# main.net
KiCad netlist of a schematic drawn in Altium Designer
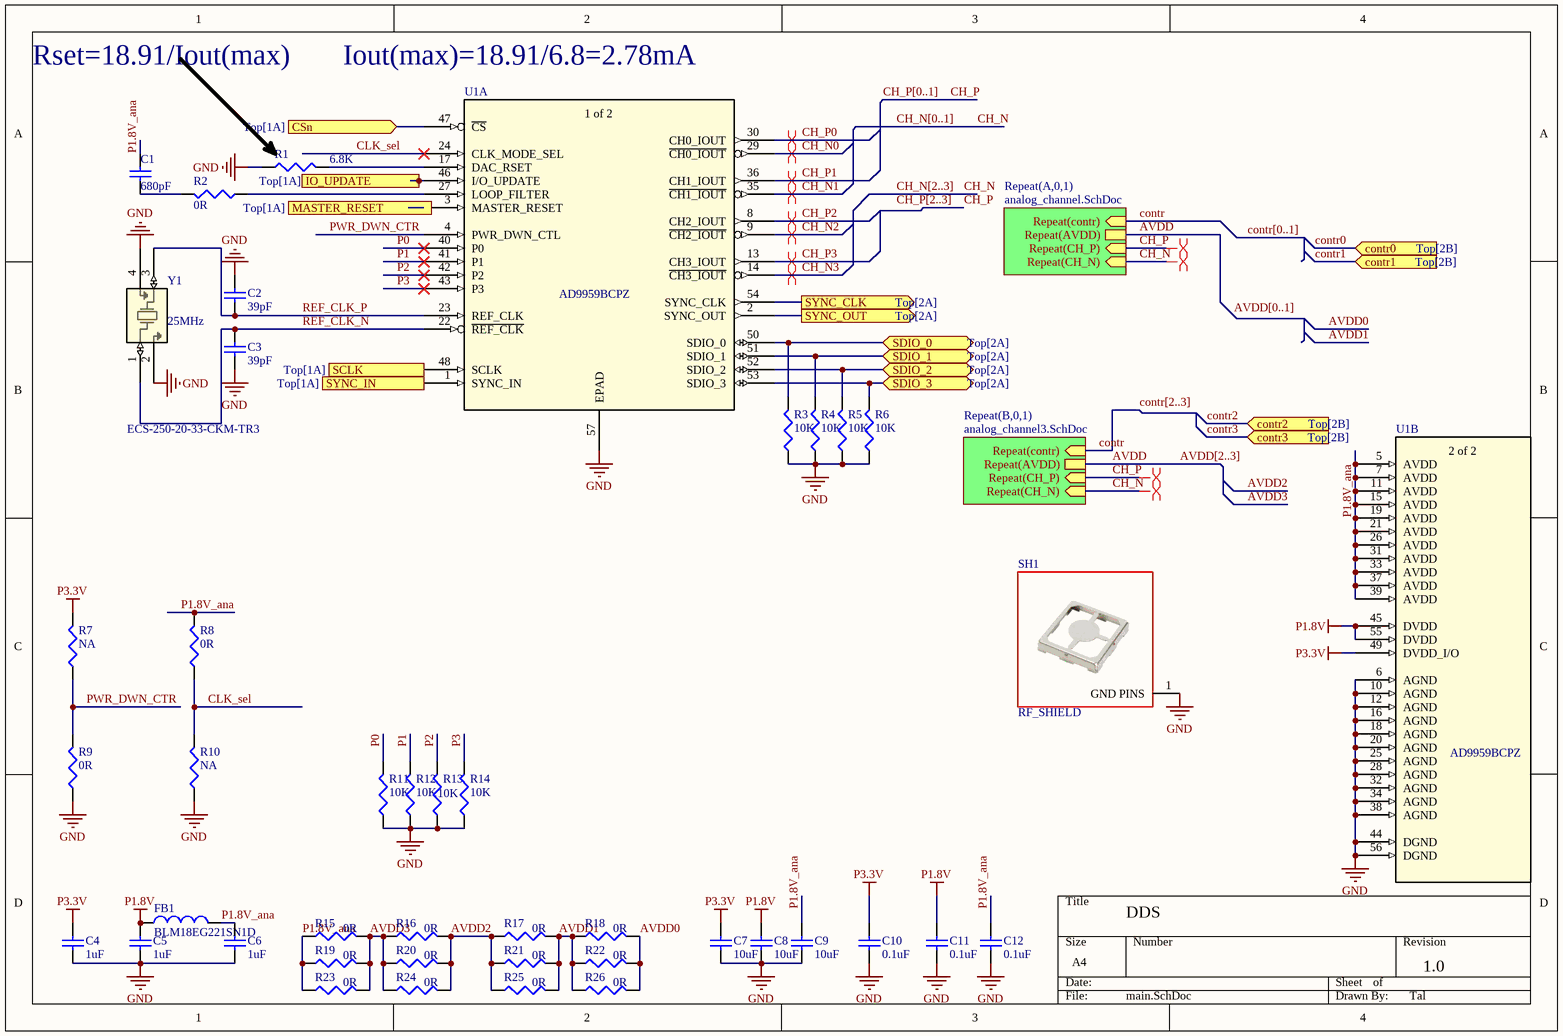
[diagram p0: main.SchDoc]

(export (version "E")
  (design (tool "Eeschema 10.0.6"))
  (components
    (comp (ref "C1")
      (value "680pF 50V")
      (footprint "C0402")
      (description "CAP CER 680PF 50V NP0 0402")
      (fields
        (field (name "MANUFACTURER PART NUMBER") "C1005C0G1H6R8D")
        (field (name "MANUFACTURER") "TDK Corporation")
        (field (name "CAPACITANCE") "680pF")
      )
      (libsource (lib "L_SCH_C") (part "CAP CER 6.8pF 50V NP0 0402"))
    )
    (comp (ref "C2")
      (value "39pF 50V")
      (footprint "C0402")
      (description "CAP CER 39PF 50V NP0 0402")
      (fields
        (field (name "MANUFACTURER PART NUMBER") "C1005C0G1H6R8D")
        (field (name "MANUFACTURER") "TDK Corporation")
        (field (name "CAPACITANCE") "39pF")
      )
      (libsource (lib "L_SCH_C") (part "CAP CER 6.8pF 50V NP0 0402"))
    )
    (comp (ref "C3")
      (value "39pF 50V")
      (footprint "C0402")
      (description "CAP CER 39PF 50V NP0 0402")
      (fields
        (field (name "MANUFACTURER PART NUMBER") "C1005C0G1H6R8D")
        (field (name "MANUFACTURER") "TDK Corporation")
        (field (name "CAPACITANCE") "39pF")
      )
      (libsource (lib "L_SCH_C") (part "CAP CER 6.8pF 50V NP0 0402"))
    )
    (comp (ref "C4")
      (value "1uF 25V")
      (footprint "C0402")
      (description "CAP CER 1uF 25V X5R 0402")
      (fields
        (field (name "MANUFACTURER PART NUMBER") "C1005C0G1H6R8D")
        (field (name "MANUFACTURER") "TDK Corporation")
        (field (name "CAPACITANCE") "1uF")
      )
      (libsource (lib "L_SCH_C") (part "CAP CER 6.8pF 50V NP0 0402"))
    )
    (comp (ref "C5")
      (value "1uF 25V")
      (footprint "C0402")
      (description "CAP CER 1uF 25V X5R 0402")
      (fields
        (field (name "MANUFACTURER PART NUMBER") "C1005C0G1H6R8D")
        (field (name "MANUFACTURER") "TDK Corporation")
        (field (name "CAPACITANCE") "1uF")
      )
      (libsource (lib "L_SCH_C") (part "CAP CER 6.8pF 50V NP0 0402"))
    )
    (comp (ref "C6")
      (value "1uF 25V")
      (footprint "C0402")
      (description "CAP CER 1uF 25V X5R 0402")
      (fields
        (field (name "MANUFACTURER PART NUMBER") "C1005C0G1H6R8D")
        (field (name "MANUFACTURER") "TDK Corporation")
        (field (name "CAPACITANCE") "1uF")
      )
      (libsource (lib "L_SCH_C") (part "CAP CER 6.8pF 50V NP0 0402"))
    )
    (comp (ref "C7")
      (value "10uF 10V")
      (footprint "C0402")
      (description "CAP CER 10uF 10V X5R 0402")
      (fields
        (field (name "MANUFACTURER PART NUMBER") "C1005C0G1H6R8D")
        (field (name "MANUFACTURER") "TDK Corporation")
        (field (name "CAPACITANCE") "10uF")
      )
      (libsource (lib "L_SCH_C") (part "CAP CER 6.8pF 50V NP0 0402"))
    )
    (comp (ref "C8")
      (value "10uF 10V")
      (footprint "C0402")
      (description "CAP CER 10uF 10V X5R 0402")
      (fields
        (field (name "MANUFACTURER PART NUMBER") "C1005C0G1H6R8D")
        (field (name "MANUFACTURER") "TDK Corporation")
        (field (name "CAPACITANCE") "10uF")
      )
      (libsource (lib "L_SCH_C") (part "CAP CER 6.8pF 50V NP0 0402"))
    )
    (comp (ref "C9")
      (value "10uF 10V")
      (footprint "C0402")
      (description "CAP CER 10uF 10V X5R 0402")
      (fields
        (field (name "MANUFACTURER PART NUMBER") "C1005C0G1H6R8D")
        (field (name "MANUFACTURER") "TDK Corporation")
        (field (name "CAPACITANCE") "10uF")
      )
      (libsource (lib "L_SCH_C") (part "CAP CER 6.8pF 50V NP0 0402"))
    )
    (comp (ref "C10")
      (value "0.1uF 50V")
      (footprint "C0402")
      (description "CAP CER 0.1uF 50V NP0 0402")
      (fields
        (field (name "MANUFACTURER PART NUMBER") "C1005C0G1H6R8D")
        (field (name "MANUFACTURER") "TDK Corporation")
        (field (name "CAPACITANCE") "0.1uF")
      )
      (libsource (lib "L_SCH_C") (part "CAP CER 6.8pF 50V NP0 0402"))
    )
    (comp (ref "C11")
      (value "0.1uF 50V")
      (footprint "C0402")
      (description "CAP CER 0.1uF 50V NP0 0402")
      (fields
        (field (name "MANUFACTURER PART NUMBER") "C1005C0G1H6R8D")
        (field (name "MANUFACTURER") "TDK Corporation")
        (field (name "CAPACITANCE") "0.1uF")
      )
      (libsource (lib "L_SCH_C") (part "CAP CER 6.8pF 50V NP0 0402"))
    )
    (comp (ref "C12")
      (value "0.1uF 50V")
      (footprint "C0402")
      (description "CAP CER 0.1uF 50V NP0 0402")
      (fields
        (field (name "MANUFACTURER PART NUMBER") "C1005C0G1H6R8D")
        (field (name "MANUFACTURER") "TDK Corporation")
        (field (name "CAPACITANCE") "0.1uF")
      )
      (libsource (lib "L_SCH_C") (part "CAP CER 6.8pF 50V NP0 0402"))
    )
    (comp (ref "FB1")
      (value "BLM18EG221SN1D")
      (footprint "fb0603")
      (description "FERRITE BEAD 220_OHM@100MHz 0603 2A 50mohm_DC")
      (fields
        (field (name "MANUFACTURER") "Taiyo Yuden")
        (field (name "MANUFACTURER PART NUMBER") "BLM18EG221SN1D")
      )
      (libsource (lib "L_SCH") (part "BK1608HS600-T"))
    )
    (comp (ref "R1")
      (value "6.8K")
      (footprint "R0402")
      (description "RES 6.8K OHM 1/16W 1% 0402")
      (fields
        (field (name "MANUFACTURER PART NUMBER") "RMCF0402FT3K09")
        (field (name "MANUFACTURER") "Stackpole Electronics Inc")
      )
      (libsource (lib "L_SCH_R") (part "RES 3.09K OHM 1/16W 1% 0402"))
    )
    (comp (ref "R2")
      (value "0R")
      (footprint "R0402")
      (description "RES 0 OHM 1/10W 1% 0402 SMD")
      (fields
        (field (name "MANUFACTURER PART NUMBER") "ERJ-2RKF1000X")
        (field (name "MANUFACTURER") "Panasonic Electronic Components")
      )
      (libsource (lib "L_SCH_R") (part "RES 100 OHM 1/10W 1% 0402 SMD"))
    )
    (comp (ref "R3")
      (value "10K")
      (footprint "R0402")
      (description "RES 10K OHM 1/16W 1% 0402")
      (fields
        (field (name "MANUFACTURER PART NUMBER") "RMCF0402FT3K09")
        (field (name "MANUFACTURER") "Stackpole Electronics Inc")
      )
      (libsource (lib "L_SCH_R") (part "RES 3.09K OHM 1/16W 1% 0402"))
    )
    (comp (ref "R4")
      (value "10K")
      (footprint "R0402")
      (description "RES 10K OHM 1/16W 1% 0402")
      (fields
        (field (name "MANUFACTURER PART NUMBER") "RMCF0402FT3K09")
        (field (name "MANUFACTURER") "Stackpole Electronics Inc")
      )
      (libsource (lib "L_SCH_R") (part "RES 3.09K OHM 1/16W 1% 0402"))
    )
    (comp (ref "R5")
      (value "10K")
      (footprint "R0402")
      (description "RES 10K OHM 1/16W 1% 0402")
      (fields
        (field (name "MANUFACTURER PART NUMBER") "RMCF0402FT3K09")
        (field (name "MANUFACTURER") "Stackpole Electronics Inc")
      )
      (libsource (lib "L_SCH_R") (part "RES 3.09K OHM 1/16W 1% 0402"))
    )
    (comp (ref "R6")
      (value "10K")
      (footprint "R0402")
      (description "RES 10K OHM 1/16W 1% 0402")
      (fields
        (field (name "MANUFACTURER PART NUMBER") "RMCF0402FT3K09")
        (field (name "MANUFACTURER") "Stackpole Electronics Inc")
      )
      (libsource (lib "L_SCH_R") (part "RES 3.09K OHM 1/16W 1% 0402"))
    )
    (comp (ref "R7")
      (value "NA")
      (footprint "R0402")
      (description "RES 0 OHM 1/10W 1% 0402 SMD")
      (fields
        (field (name "MANUFACTURER PART NUMBER") "ERJ-2RKF1000X")
        (field (name "MANUFACTURER") "Panasonic Electronic Components")
      )
      (libsource (lib "L_SCH_R") (part "RES 100 OHM 1/10W 1% 0402 SMD"))
    )
    (comp (ref "R8")
      (value "0R")
      (footprint "R0402")
      (description "RES 0 OHM 1/10W 1% 0402 SMD")
      (fields
        (field (name "MANUFACTURER PART NUMBER") "ERJ-2RKF1000X")
        (field (name "MANUFACTURER") "Panasonic Electronic Components")
      )
      (libsource (lib "L_SCH_R") (part "RES 100 OHM 1/10W 1% 0402 SMD"))
    )
    (comp (ref "R9")
      (value "0R")
      (footprint "R0402")
      (description "RES 0 OHM 1/10W 1% 0402 SMD")
      (fields
        (field (name "MANUFACTURER PART NUMBER") "ERJ-2RKF1000X")
        (field (name "MANUFACTURER") "Panasonic Electronic Components")
      )
      (libsource (lib "L_SCH_R") (part "RES 100 OHM 1/10W 1% 0402 SMD"))
    )
    (comp (ref "R10")
      (value "NA")
      (footprint "R0402")
      (description "RES 0 OHM 1/10W 1% 0402 SMD")
      (fields
        (field (name "MANUFACTURER PART NUMBER") "ERJ-2RKF1000X")
        (field (name "MANUFACTURER") "Panasonic Electronic Components")
      )
      (libsource (lib "L_SCH_R") (part "RES 100 OHM 1/10W 1% 0402 SMD"))
    )
    (comp (ref "R11")
      (value "10K")
      (footprint "R0402")
      (description "RES 10K OHM 1/16W 1% 0402")
      (fields
        (field (name "MANUFACTURER PART NUMBER") "RMCF0402FT3K09")
        (field (name "MANUFACTURER") "Stackpole Electronics Inc")
      )
      (libsource (lib "L_SCH_R") (part "RES 3.09K OHM 1/16W 1% 0402"))
    )
    (comp (ref "R12")
      (value "10K")
      (footprint "R0402")
      (description "RES 10K OHM 1/16W 1% 0402")
      (fields
        (field (name "MANUFACTURER PART NUMBER") "RMCF0402FT3K09")
        (field (name "MANUFACTURER") "Stackpole Electronics Inc")
      )
      (libsource (lib "L_SCH_R") (part "RES 3.09K OHM 1/16W 1% 0402"))
    )
    (comp (ref "R13")
      (value "10K")
      (footprint "R0402")
      (description "RES 10K OHM 1/16W 1% 0402")
      (fields
        (field (name "MANUFACTURER PART NUMBER") "RMCF0402FT3K09")
        (field (name "MANUFACTURER") "Stackpole Electronics Inc")
      )
      (libsource (lib "L_SCH_R") (part "RES 3.09K OHM 1/16W 1% 0402"))
    )
    (comp (ref "R14")
      (value "10K")
      (footprint "R0402")
      (description "RES 10K OHM 1/16W 1% 0402")
      (fields
        (field (name "MANUFACTURER PART NUMBER") "RMCF0402FT3K09")
        (field (name "MANUFACTURER") "Stackpole Electronics Inc")
      )
      (libsource (lib "L_SCH_R") (part "RES 3.09K OHM 1/16W 1% 0402"))
    )
    (comp (ref "R15")
      (value "0R")
      (footprint "R0805")
      (description "RES 0 OHM 1/8W 1% 0805 SMD")
      (fields
        (field (name "MANUFACTURER PART NUMBER") "RMCF0805FT200R")
        (field (name "MANUFACTURER") "Stackpole Electronics Inc")
      )
      (libsource (lib "L_SCH_R") (part "RES 200 OHM 1/8W 1% 0805 SMD"))
    )
    (comp (ref "R16")
      (value "0R")
      (footprint "R0805")
      (description "RES 0 OHM 1/8W 1% 0805 SMD")
      (fields
        (field (name "MANUFACTURER PART NUMBER") "RMCF0805FT200R")
        (field (name "MANUFACTURER") "Stackpole Electronics Inc")
      )
      (libsource (lib "L_SCH_R") (part "RES 200 OHM 1/8W 1% 0805 SMD"))
    )
    (comp (ref "R17")
      (value "0R")
      (footprint "R0805")
      (description "RES 0 OHM 1/8W 1% 0805 SMD")
      (fields
        (field (name "MANUFACTURER PART NUMBER") "RMCF0805FT200R")
        (field (name "MANUFACTURER") "Stackpole Electronics Inc")
      )
      (libsource (lib "L_SCH_R") (part "RES 200 OHM 1/8W 1% 0805 SMD"))
    )
    (comp (ref "R18")
      (value "0R")
      (footprint "R0805")
      (description "RES 0 OHM 1/8W 1% 0805 SMD")
      (fields
        (field (name "MANUFACTURER PART NUMBER") "RMCF0805FT200R")
        (field (name "MANUFACTURER") "Stackpole Electronics Inc")
      )
      (libsource (lib "L_SCH_R") (part "RES 200 OHM 1/8W 1% 0805 SMD"))
    )
    (comp (ref "R19")
      (value "0R")
      (footprint "R0805")
      (description "RES 0 OHM 1/8W 1% 0805 SMD")
      (fields
        (field (name "MANUFACTURER PART NUMBER") "RMCF0805FT200R")
        (field (name "MANUFACTURER") "Stackpole Electronics Inc")
      )
      (libsource (lib "L_SCH_R") (part "RES 200 OHM 1/8W 1% 0805 SMD"))
    )
    (comp (ref "R20")
      (value "0R")
      (footprint "R0805")
      (description "RES 0 OHM 1/8W 1% 0805 SMD")
      (fields
        (field (name "MANUFACTURER PART NUMBER") "RMCF0805FT200R")
        (field (name "MANUFACTURER") "Stackpole Electronics Inc")
      )
      (libsource (lib "L_SCH_R") (part "RES 200 OHM 1/8W 1% 0805 SMD"))
    )
    (comp (ref "R21")
      (value "0R")
      (footprint "R0805")
      (description "RES 0 OHM 1/8W 1% 0805 SMD")
      (fields
        (field (name "MANUFACTURER PART NUMBER") "RMCF0805FT200R")
        (field (name "MANUFACTURER") "Stackpole Electronics Inc")
      )
      (libsource (lib "L_SCH_R") (part "RES 200 OHM 1/8W 1% 0805 SMD"))
    )
    (comp (ref "R22")
      (value "0R")
      (footprint "R0805")
      (description "RES 0 OHM 1/8W 1% 0805 SMD")
      (fields
        (field (name "MANUFACTURER PART NUMBER") "RMCF0805FT200R")
        (field (name "MANUFACTURER") "Stackpole Electronics Inc")
      )
      (libsource (lib "L_SCH_R") (part "RES 200 OHM 1/8W 1% 0805 SMD"))
    )
    (comp (ref "R23")
      (value "0R")
      (footprint "R0805")
      (description "RES 0 OHM 1/8W 1% 0805 SMD")
      (fields
        (field (name "MANUFACTURER PART NUMBER") "RMCF0805FT200R")
        (field (name "MANUFACTURER") "Stackpole Electronics Inc")
      )
      (libsource (lib "L_SCH_R") (part "RES 200 OHM 1/8W 1% 0805 SMD"))
    )
    (comp (ref "R24")
      (value "0R")
      (footprint "R0805")
      (description "RES 0 OHM 1/8W 1% 0805 SMD")
      (fields
        (field (name "MANUFACTURER PART NUMBER") "RMCF0805FT200R")
        (field (name "MANUFACTURER") "Stackpole Electronics Inc")
      )
      (libsource (lib "L_SCH_R") (part "RES 200 OHM 1/8W 1% 0805 SMD"))
    )
    (comp (ref "R25")
      (value "0R")
      (footprint "R0805")
      (description "RES 0 OHM 1/8W 1% 0805 SMD")
      (fields
        (field (name "MANUFACTURER PART NUMBER") "RMCF0805FT200R")
        (field (name "MANUFACTURER") "Stackpole Electronics Inc")
      )
      (libsource (lib "L_SCH_R") (part "RES 200 OHM 1/8W 1% 0805 SMD"))
    )
    (comp (ref "R26")
      (value "0R")
      (footprint "R0805")
      (description "RES 0 OHM 1/8W 1% 0805 SMD")
      (fields
        (field (name "MANUFACTURER PART NUMBER") "RMCF0805FT200R")
        (field (name "MANUFACTURER") "Stackpole Electronics Inc")
      )
      (libsource (lib "L_SCH_R") (part "RES 200 OHM 1/8W 1% 0805 SMD"))
    )
    (comp (ref "SH1")
      (value "RF_SHIELD")
      (footprint "SMS201F")
      (description "RF SHIELD 0.5\" X 0.538\" SMD")
      (fields
        (field (name "MANUFACTURER_PART_NUMBER") "SMS-201F")
        (field (name "MANUFACTURER") "Leader Tech Inc.")
      )
      (libsource (lib "DDS_PCB_1") (part "RF_SHIELD"))
    )
    (comp (ref "U1")
      (value "AD9959BCPZ")
      (footprint "CP_56_1_ADI")
      (description "No Description Available")
      (fields (field (name "COPYRIGHT") "Copyright (C) 2023 Ultra Librarian. All rights reserved."))
      (libsource (lib "") (part "AD9959BCPZ_1"))
    )
    (comp (ref "Y1")
      (value "ECS-250-20-33-CKM-TR3")
      (footprint "SMD4_ECX-32_3p2x2p5_ECS")
      (description "No Description Available")
      (fields (field (name "COPYRIGHT") "Copyright (C) 2023 Ultra Librarian. All rights reserved."))
      (libsource (lib "ECS-250-20-33-CKM-TR3") (part "ECS-250-20-33-CKM-TR3"))
    )
  )
  (nets
    (net (code "2") (name "/AVDD0") (class "Default")
      (node (ref "R18") (pin "2") (pinfunction "2_2") (pintype "passive"))
      (node (ref "R22") (pin "2") (pinfunction "2_2") (pintype "passive"))
      (node (ref "R26") (pin "2") (pinfunction "2_2") (pintype "passive"))
    )
    (net (code "3") (name "/AVDD1") (class "Default")
      (node (ref "R17") (pin "2") (pinfunction "2_2") (pintype "passive"))
      (node (ref "R18") (pin "1") (pinfunction "1_1") (pintype "passive"))
      (node (ref "R21") (pin "2") (pinfunction "2_2") (pintype "passive"))
      (node (ref "R22") (pin "1") (pinfunction "1_1") (pintype "passive"))
      (node (ref "R25") (pin "2") (pinfunction "2_2") (pintype "passive"))
      (node (ref "R26") (pin "1") (pinfunction "1_1") (pintype "passive"))
    )
    (net (code "4") (name "/AVDD2") (class "Default")
      (node (ref "R16") (pin "2") (pinfunction "2_2") (pintype "passive"))
      (node (ref "R17") (pin "1") (pinfunction "1_1") (pintype "passive"))
      (node (ref "R20") (pin "2") (pinfunction "2_2") (pintype "passive"))
      (node (ref "R21") (pin "1") (pinfunction "1_1") (pintype "passive"))
      (node (ref "R24") (pin "2") (pinfunction "2_2") (pintype "passive"))
      (node (ref "R25") (pin "1") (pinfunction "1_1") (pintype "passive"))
    )
    (net (code "5") (name "/AVDD3") (class "Default")
      (node (ref "R15") (pin "2") (pinfunction "2_2") (pintype "passive"))
      (node (ref "R16") (pin "1") (pinfunction "1_1") (pintype "passive"))
      (node (ref "R19") (pin "2") (pinfunction "2_2") (pintype "passive"))
      (node (ref "R20") (pin "1") (pinfunction "1_1") (pintype "passive"))
      (node (ref "R23") (pin "2") (pinfunction "2_2") (pintype "passive"))
      (node (ref "R24") (pin "1") (pinfunction "1_1") (pintype "passive"))
    )
    (net (code "8") (name "/CH_N0") (class "Default")
      (node (ref "U1") (pin "29") (pinfunction "~{CH0_IOUT}_29") (pintype "output"))
    )
    (net (code "9") (name "/CH_N1") (class "Default")
      (node (ref "U1") (pin "35") (pinfunction "~{CH1_IOUT}_35") (pintype "output"))
    )
    (net (code "10") (name "/CH_N2") (class "Default")
      (node (ref "U1") (pin "9") (pinfunction "~{CH2_IOUT}_9") (pintype "output"))
    )
    (net (code "11") (name "/CH_N3") (class "Default")
      (node (ref "U1") (pin "14") (pinfunction "~{CH3_IOUT}_14") (pintype "output"))
    )
    (net (code "15") (name "/CH_P0") (class "Default")
      (node (ref "U1") (pin "30") (pinfunction "CH0_IOUT_30") (pintype "output"))
    )
    (net (code "16") (name "/CH_P1") (class "Default")
      (node (ref "U1") (pin "36") (pinfunction "CH1_IOUT_36") (pintype "output"))
    )
    (net (code "17") (name "/CH_P2") (class "Default")
      (node (ref "U1") (pin "8") (pinfunction "CH2_IOUT_8") (pintype "output"))
    )
    (net (code "18") (name "/CH_P3") (class "Default")
      (node (ref "U1") (pin "13") (pinfunction "CH3_IOUT_13") (pintype "output"))
    )
    (net (code "21") (name "/CLK_sel") (class "Default")
      (node (ref "R10") (pin "2") (pinfunction "2_2") (pintype "passive"))
      (node (ref "R8") (pin "1") (pinfunction "1_1") (pintype "passive"))
      (node (ref "U1") (pin "24") (pinfunction "CLK_MODE_SEL_24") (pintype "input"))
    )
    (net (code "22") (name "/CSn") (class "Default")
      (node (ref "U1") (pin "47") (pinfunction "~{CS}_47") (pintype "input"))
    )
    (net (code "23") (name "/IO_UPDATE") (class "Default")
      (node (ref "U1") (pin "46") (pinfunction "I/O_UPDATE_46") (pintype "input"))
    )
    (net (code "25") (name "/P0") (class "Default")
      (node (ref "R11") (pin "2") (pinfunction "2_2") (pintype "passive"))
      (node (ref "U1") (pin "40") (pinfunction "P0_40") (pintype "input"))
    )
    (net (code "26") (name "/P1") (class "Default")
      (node (ref "R12") (pin "2") (pinfunction "2_2") (pintype "passive"))
      (node (ref "U1") (pin "41") (pinfunction "P1_41") (pintype "input"))
    )
    (net (code "27") (name "/P1.8V_ana") (class "Default")
      (node (ref "C1") (pin "1") (pinfunction "1_1") (pintype "passive"))
      (node (ref "C12") (pin "2") (pinfunction "2_2") (pintype "passive"))
      (node (ref "C6") (pin "2") (pinfunction "2_2") (pintype "passive"))
      (node (ref "C9") (pin "2") (pinfunction "2_2") (pintype "passive"))
      (node (ref "FB1") (pin "2") (pinfunction "2_2") (pintype "passive"))
      (node (ref "R15") (pin "1") (pinfunction "1_1") (pintype "passive"))
      (node (ref "R19") (pin "1") (pinfunction "1_1") (pintype "passive"))
      (node (ref "R23") (pin "1") (pinfunction "1_1") (pintype "passive"))
      (node (ref "R8") (pin "2") (pinfunction "2_2") (pintype "passive"))
      (node (ref "U1") (pin "11") (pinfunction "AVDD_11") (pintype "input"))
      (node (ref "U1") (pin "15") (pinfunction "AVDD_15") (pintype "input"))
      (node (ref "U1") (pin "19") (pinfunction "AVDD_19") (pintype "input"))
      (node (ref "U1") (pin "21") (pinfunction "AVDD_21") (pintype "input"))
      (node (ref "U1") (pin "26") (pinfunction "AVDD_26") (pintype "input"))
      (node (ref "U1") (pin "31") (pinfunction "AVDD_31") (pintype "input"))
      (node (ref "U1") (pin "33") (pinfunction "AVDD_33") (pintype "input"))
      (node (ref "U1") (pin "37") (pinfunction "AVDD_37") (pintype "input"))
      (node (ref "U1") (pin "39") (pinfunction "AVDD_39") (pintype "input"))
      (node (ref "U1") (pin "5") (pinfunction "AVDD_5") (pintype "input"))
      (node (ref "U1") (pin "7") (pinfunction "AVDD_7") (pintype "input"))
    )
    (net (code "28") (name "/P2") (class "Default")
      (node (ref "R13") (pin "2") (pinfunction "2_2") (pintype "passive"))
      (node (ref "U1") (pin "42") (pinfunction "P2_42") (pintype "input"))
    )
    (net (code "29") (name "/P3") (class "Default")
      (node (ref "R14") (pin "2") (pinfunction "2_2") (pintype "passive"))
      (node (ref "U1") (pin "43") (pinfunction "P3_43") (pintype "input"))
    )
    (net (code "30") (name "/PWR_DWN_CTR") (class "Default")
      (node (ref "R7") (pin "1") (pinfunction "1_1") (pintype "passive"))
      (node (ref "R9") (pin "2") (pinfunction "2_2") (pintype "passive"))
      (node (ref "U1") (pin "4") (pinfunction "PWR_DWN_CTL_4") (pintype "input"))
    )
    (net (code "31") (name "/REF_CLK_N") (class "Default")
      (node (ref "C3") (pin "2") (pinfunction "2_2") (pintype "passive"))
      (node (ref "U1") (pin "22") (pinfunction "~{REF_CLK}_22") (pintype "input"))
      (node (ref "Y1") (pin "1") (pinfunction "1_1") (pintype "bidirectional"))
    )
    (net (code "32") (name "/REF_CLK_P") (class "Default")
      (node (ref "C2") (pin "1") (pinfunction "1_1") (pintype "passive"))
      (node (ref "U1") (pin "23") (pinfunction "REF_CLK_23") (pintype "input"))
      (node (ref "Y1") (pin "3") (pinfunction "3_3") (pintype "bidirectional"))
    )
    (net (code "33") (name "/SCLK") (class "Default")
      (node (ref "U1") (pin "48") (pinfunction "SCLK_48") (pintype "input"))
    )
    (net (code "34") (name "/SDIO_0") (class "Default")
      (node (ref "R3") (pin "2") (pinfunction "2_2") (pintype "passive"))
      (node (ref "U1") (pin "50") (pinfunction "SDIO_0_50") (pintype "bidirectional"))
    )
    (net (code "35") (name "/SDIO_1") (class "Default")
      (node (ref "R4") (pin "2") (pinfunction "2_2") (pintype "passive"))
      (node (ref "U1") (pin "51") (pinfunction "SDIO_1_51") (pintype "bidirectional"))
    )
    (net (code "36") (name "/SDIO_2") (class "Default")
      (node (ref "R5") (pin "2") (pinfunction "2_2") (pintype "passive"))
      (node (ref "U1") (pin "52") (pinfunction "SDIO_2_52") (pintype "bidirectional"))
    )
    (net (code "37") (name "/SDIO_3") (class "Default")
      (node (ref "R6") (pin "2") (pinfunction "2_2") (pintype "passive"))
      (node (ref "U1") (pin "53") (pinfunction "SDIO_3_53") (pintype "bidirectional"))
    )
    (net (code "38") (name "/SYNC_CLK") (class "Default")
      (node (ref "U1") (pin "54") (pinfunction "SYNC_CLK_54") (pintype "output"))
    )
    (net (code "39") (name "/SYNC_IN") (class "Default")
      (node (ref "U1") (pin "1") (pinfunction "SYNC_IN_1") (pintype "input"))
    )
    (net (code "40") (name "/SYNC_OUT") (class "Default")
      (node (ref "U1") (pin "2") (pinfunction "SYNC_OUT_2") (pintype "output"))
    )
    (net (code "47") (name "GND") (class "Default")
      (node (ref "C10") (pin "1") (pinfunction "1_1") (pintype "passive"))
      (node (ref "C11") (pin "1") (pinfunction "1_1") (pintype "passive"))
      (node (ref "C12") (pin "1") (pinfunction "1_1") (pintype "passive"))
      (node (ref "C2") (pin "2") (pinfunction "2_2") (pintype "passive"))
      (node (ref "C3") (pin "1") (pinfunction "1_1") (pintype "passive"))
      (node (ref "C4") (pin "1") (pinfunction "1_1") (pintype "passive"))
      (node (ref "C5") (pin "1") (pinfunction "1_1") (pintype "passive"))
      (node (ref "C6") (pin "1") (pinfunction "1_1") (pintype "passive"))
      (node (ref "C7") (pin "1") (pinfunction "1_1") (pintype "passive"))
      (node (ref "C8") (pin "1") (pinfunction "1_1") (pintype "passive"))
      (node (ref "C9") (pin "1") (pinfunction "1_1") (pintype "passive"))
      (node (ref "R1") (pin "1") (pinfunction "1_1") (pintype "passive"))
      (node (ref "R10") (pin "1") (pinfunction "1_1") (pintype "passive"))
      (node (ref "R11") (pin "1") (pinfunction "1_1") (pintype "passive"))
      (node (ref "R12") (pin "1") (pinfunction "1_1") (pintype "passive"))
      (node (ref "R13") (pin "1") (pinfunction "1_1") (pintype "passive"))
      (node (ref "R14") (pin "1") (pinfunction "1_1") (pintype "passive"))
      (node (ref "R3") (pin "1") (pinfunction "1_1") (pintype "passive"))
      (node (ref "R4") (pin "1") (pinfunction "1_1") (pintype "passive"))
      (node (ref "R5") (pin "1") (pinfunction "1_1") (pintype "passive"))
      (node (ref "R6") (pin "1") (pinfunction "1_1") (pintype "passive"))
      (node (ref "R9") (pin "1") (pinfunction "1_1") (pintype "passive"))
      (node (ref "SH1") (pin "1") (pinfunction "GND_PINS_1") (pintype "passive"))
      (node (ref "U1") (pin "10") (pinfunction "AGND_10") (pintype "input"))
      (node (ref "U1") (pin "12") (pinfunction "AGND_12") (pintype "input"))
      (node (ref "U1") (pin "16") (pinfunction "AGND_16") (pintype "input"))
      (node (ref "U1") (pin "18") (pinfunction "AGND_18") (pintype "input"))
      (node (ref "U1") (pin "20") (pinfunction "AGND_20") (pintype "input"))
      (node (ref "U1") (pin "25") (pinfunction "AGND_25") (pintype "input"))
      (node (ref "U1") (pin "28") (pinfunction "AGND_28") (pintype "input"))
      (node (ref "U1") (pin "32") (pinfunction "AGND_32") (pintype "input"))
      (node (ref "U1") (pin "34") (pinfunction "AGND_34") (pintype "input"))
      (node (ref "U1") (pin "38") (pinfunction "AGND_38") (pintype "input"))
      (node (ref "U1") (pin "44") (pinfunction "DGND_44") (pintype "input"))
      (node (ref "U1") (pin "56") (pinfunction "DGND_56") (pintype "input"))
      (node (ref "U1") (pin "57") (pinfunction "EPAD_57") (pintype "passive"))
      (node (ref "U1") (pin "6") (pinfunction "AGND_6") (pintype "input"))
      (node (ref "Y1") (pin "2") (pinfunction "2_2") (pintype "passive"))
      (node (ref "Y1") (pin "4") (pinfunction "4_4") (pintype "passive"))
    )
    (net (code "48") (name "Net-(C1-Pad2)") (class "Default")
      (node (ref "C1") (pin "2") (pinfunction "2_2") (pintype "passive"))
      (node (ref "R2") (pin "2") (pinfunction "2_2") (pintype "passive"))
    )
    (net (code "49") (name "Net-(U1A-DAC_RSET)") (class "Default")
      (node (ref "R1") (pin "2") (pinfunction "2_2") (pintype "passive"))
      (node (ref "U1") (pin "17") (pinfunction "DAC_RSET_17") (pintype "input"))
    )
    (net (code "50") (name "Net-(U1A-LOOP_FILTER)") (class "Default")
      (node (ref "R2") (pin "1") (pinfunction "1_1") (pintype "passive"))
      (node (ref "U1") (pin "27") (pinfunction "LOOP_FILTER_27") (pintype "input"))
    )
    (net (code "51") (name "P1.8V") (class "Default")
      (node (ref "C11") (pin "2") (pinfunction "2_2") (pintype "passive"))
      (node (ref "C5") (pin "2") (pinfunction "2_2") (pintype "passive"))
      (node (ref "C8") (pin "2") (pinfunction "2_2") (pintype "passive"))
      (node (ref "FB1") (pin "1") (pinfunction "1_1") (pintype "passive"))
      (node (ref "U1") (pin "45") (pinfunction "DVDD_45") (pintype "input"))
      (node (ref "U1") (pin "55") (pinfunction "DVDD_55") (pintype "input"))
    )
    (net (code "52") (name "P3.3V") (class "Default")
      (node (ref "C10") (pin "2") (pinfunction "2_2") (pintype "passive"))
      (node (ref "C4") (pin "2") (pinfunction "2_2") (pintype "passive"))
      (node (ref "C7") (pin "2") (pinfunction "2_2") (pintype "passive"))
      (node (ref "R7") (pin "2") (pinfunction "2_2") (pintype "passive"))
      (node (ref "U1") (pin "49") (pinfunction "DVDD_I/O_49") (pintype "input"))
    )
    (net (code "53") (name "unconnected-(U1A-MASTER_RESET-Pad3)") (class "Default")
      (node (ref "U1") (pin "3") (pinfunction "MASTER_RESET_3") (pintype "input"))
    )
  )
)
